# Power_supply.net
KiCad netlist of a schematic drawn in Altium Designer
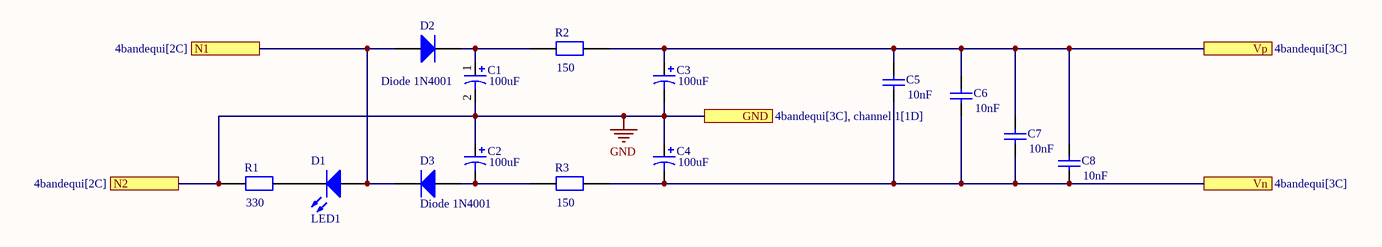
[diagram p0: Power supply.SchDoc]

(export (version "E")
  (design (tool "Eeschema 10.0.6"))
  (components
    (comp (ref "C1")
      (value "100uF")
      (footprint "pol. cap.")
      (description "Polarized Capacitor (Radial)")
      (fields (field (name "Comment") "Cap Pol1") (field (name "PUBLISHER") "Altium Limited"))
      (libsource (lib "") (part "Cap Pol1_1"))
    )
    (comp (ref "C2")
      (value "100uF")
      (footprint "pol. cap.")
      (description "Polarized Capacitor (Radial)")
      (fields (field (name "Comment") "Cap Pol1") (field (name "PUBLISHER") "Altium Limited"))
      (libsource (lib "Miscellaneous Devices") (part "Cap Pol1"))
    )
    (comp (ref "C3")
      (value "100uF")
      (footprint "pol. cap.")
      (description "Polarized Capacitor (Radial)")
      (fields (field (name "Comment") "Cap Pol1") (field (name "PUBLISHER") "Altium Limited"))
      (libsource (lib "Miscellaneous Devices") (part "Cap Pol1"))
    )
    (comp (ref "C4")
      (value "100uF")
      (footprint "pol. cap.")
      (description "Polarized Capacitor (Radial)")
      (fields (field (name "Comment") "Cap Pol1") (field (name "PUBLISHER") "Altium Limited"))
      (libsource (lib "Miscellaneous Devices") (part "Cap Pol1"))
    )
    (comp (ref "C5")
      (value "10nF")
      (footprint "Capacitor")
      (description "Capacitor")
      (fields (field (name "Comment") "Cap") (field (name "PUBLISHER") "Altium Limited"))
      (libsource (lib "Miscellaneous Devices") (part "Cap"))
    )
    (comp (ref "C6")
      (value "10nF")
      (footprint "Capacitor")
      (description "Capacitor")
      (fields (field (name "Comment") "Cap") (field (name "PUBLISHER") "Altium Limited"))
      (libsource (lib "Miscellaneous Devices") (part "Cap"))
    )
    (comp (ref "C7")
      (value "10nF")
      (footprint "Capacitor")
      (description "Capacitor")
      (fields (field (name "Comment") "Cap") (field (name "PUBLISHER") "Altium Limited"))
      (libsource (lib "Miscellaneous Devices") (part "Cap"))
    )
    (comp (ref "C8")
      (value "10nF")
      (footprint "Capacitor")
      (description "Capacitor")
      (fields (field (name "Comment") "Cap") (field (name "PUBLISHER") "Altium Limited"))
      (libsource (lib "Miscellaneous Devices") (part "Cap"))
    )
    (comp (ref "D1")
      (value "LED1")
      (footprint "LED")
      (description "Typical RED GaAs LED")
      (fields (field (name "PUBLISHER") "Altium Limited"))
      (libsource (lib "Miscellaneous Devices") (part "LED1"))
    )
    (comp (ref "D2")
      (value "Diode 1N4001")
      (footprint "DO-41")
      (description "1 Amp General Purpose Rectifier")
      (fields (field (name "PUBLISHER") "Altium Limited"))
      (libsource (lib "Miscellaneous Devices") (part "Diode 1N4001"))
    )
    (comp (ref "D3")
      (value "Diode 1N4001")
      (footprint "DO-41")
      (description "1 Amp General Purpose Rectifier")
      (fields (field (name "PUBLISHER") "Altium Limited"))
      (libsource (lib "Miscellaneous Devices") (part "Diode 1N4001"))
    )
    (comp (ref "R1")
      (value "330")
      (footprint "resistor")
      (description "resistor")
      (fields (field (name "Comment") "Resistor_Axial"))
      (libsource (lib "4bandequi") (part "Resistor_Axial"))
    )
    (comp (ref "R2")
      (value "150")
      (footprint "resistor")
      (description "resistor")
      (fields (field (name "Comment") "Resistor_Axial"))
      (libsource (lib "4bandequi") (part "Resistor_Axial"))
    )
    (comp (ref "R3")
      (value "150")
      (footprint "resistor")
      (description "resistor")
      (fields (field (name "Comment") "Resistor_Axial"))
      (libsource (lib "4bandequi") (part "Resistor_Axial"))
    )
  )
  (nets
    (net (code "1") (name "/N1") (class "Default")
      (node (ref "D1") (pin "1") (pinfunction "A_1") (pintype "passive"))
      (node (ref "D2") (pin "1") (pinfunction "A_1") (pintype "passive"))
      (node (ref "D3") (pin "2") (pinfunction "K_2") (pintype "passive"))
    )
    (net (code "2") (name "/Vn") (class "Default")
      (node (ref "C4") (pin "2") (pinfunction "2_2") (pintype "passive"))
      (node (ref "C5") (pin "2") (pinfunction "2_2") (pintype "passive"))
      (node (ref "C6") (pin "2") (pinfunction "2_2") (pintype "passive"))
      (node (ref "C7") (pin "2") (pinfunction "2_2") (pintype "passive"))
      (node (ref "C8") (pin "2") (pinfunction "2_2") (pintype "passive"))
      (node (ref "R3") (pin "2") (pinfunction "2_2") (pintype "passive"))
    )
    (net (code "3") (name "/Vp") (class "Default")
      (node (ref "C3") (pin "1") (pinfunction "1_1") (pintype "passive"))
      (node (ref "C5") (pin "1") (pinfunction "1_1") (pintype "passive"))
      (node (ref "C6") (pin "1") (pinfunction "1_1") (pintype "passive"))
      (node (ref "C7") (pin "1") (pinfunction "1_1") (pintype "passive"))
      (node (ref "C8") (pin "1") (pinfunction "1_1") (pintype "passive"))
      (node (ref "R2") (pin "2") (pinfunction "2_2") (pintype "passive"))
    )
    (net (code "4") (name "GND") (class "Default")
      (node (ref "C1") (pin "2") (pinfunction "2_2") (pintype "passive"))
      (node (ref "C2") (pin "1") (pinfunction "1_1") (pintype "passive"))
      (node (ref "C3") (pin "2") (pinfunction "2_2") (pintype "passive"))
      (node (ref "C4") (pin "1") (pinfunction "1_1") (pintype "passive"))
      (node (ref "R1") (pin "1") (pinfunction "1_1") (pintype "passive"))
    )
    (net (code "5") (name "Net-(D1-K)") (class "Default")
      (node (ref "D1") (pin "2") (pinfunction "K_2") (pintype "passive"))
      (node (ref "R1") (pin "2") (pinfunction "2_2") (pintype "passive"))
    )
    (net (code "6") (name "Net-(D2-K)") (class "Default")
      (node (ref "C1") (pin "1") (pinfunction "1_1") (pintype "passive"))
      (node (ref "D2") (pin "2") (pinfunction "K_2") (pintype "passive"))
      (node (ref "R2") (pin "1") (pinfunction "1_1") (pintype "passive"))
    )
    (net (code "7") (name "Net-(D3-A)") (class "Default")
      (node (ref "C2") (pin "2") (pinfunction "2_2") (pintype "passive"))
      (node (ref "D3") (pin "1") (pinfunction "A_1") (pintype "passive"))
      (node (ref "R3") (pin "1") (pinfunction "1_1") (pintype "passive"))
    )
  )
)
